# Schematic.net
KiCad netlist of a schematic drawn in EAGLE
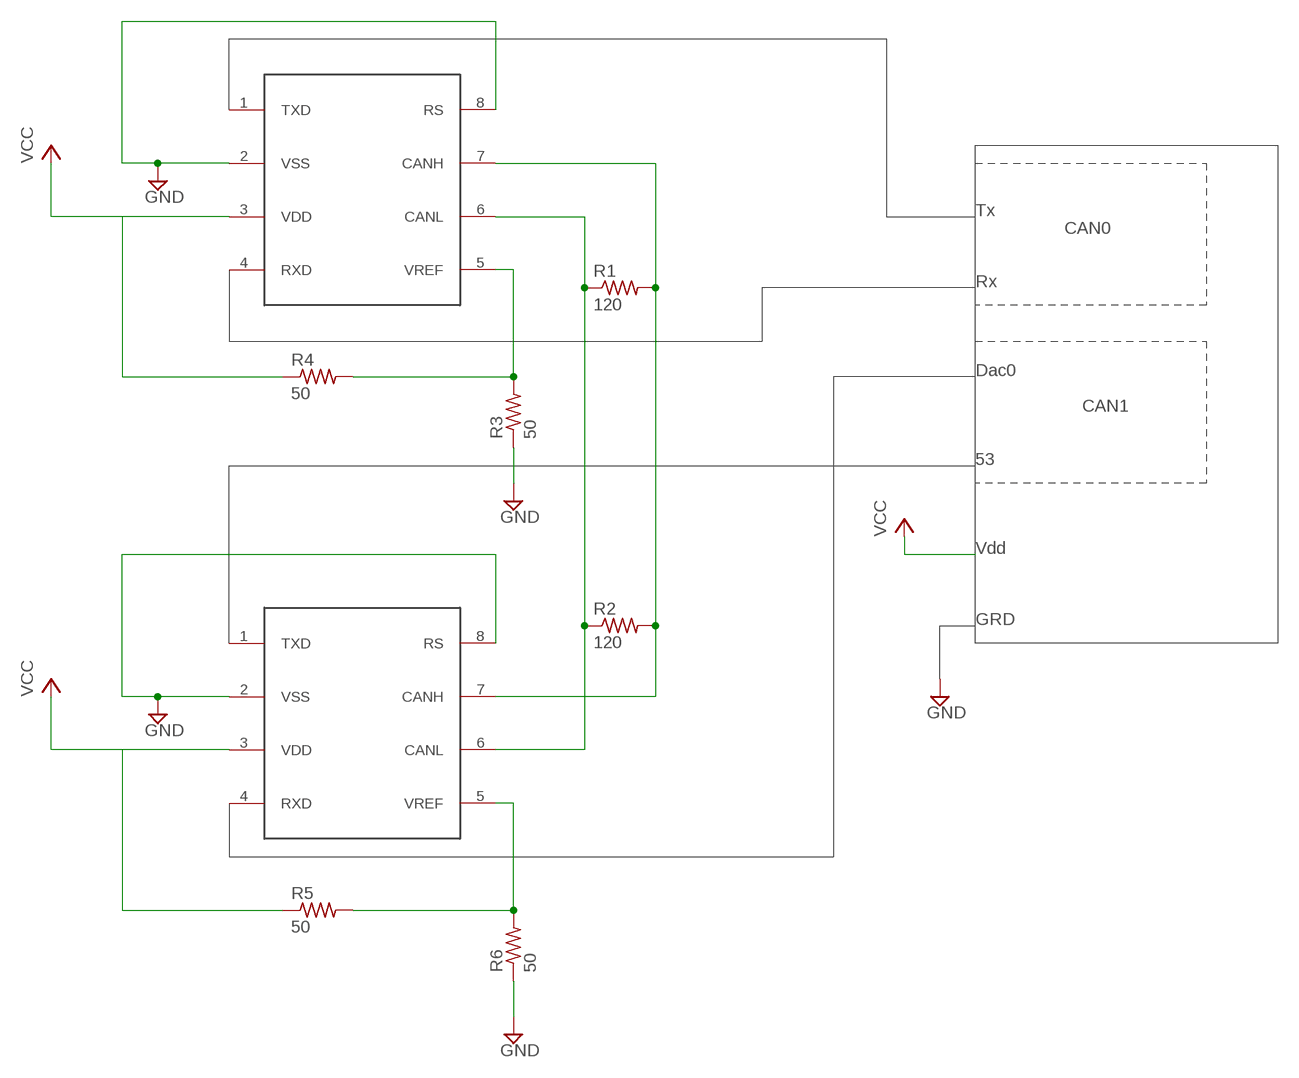
[diagram p0: schematic, sheet 1]

(export (version "E")
  (design (tool "Eeschema 10.0.6"))
  (components
    (comp (ref "R1")
      (value "120")
      (footprint "eagle-import:R0805")
      (libsource (lib "eagle-import") (part "RESISTOR"))
    )
    (comp (ref "R2")
      (value "120")
      (footprint "eagle-import:R0805")
      (libsource (lib "eagle-import") (part "RESISTOR"))
    )
    (comp (ref "R3")
      (value "50")
      (footprint "eagle-import:R0805")
      (libsource (lib "eagle-import") (part "RESISTOR"))
    )
    (comp (ref "R4")
      (value "50")
      (footprint "eagle-import:R0805")
      (libsource (lib "eagle-import") (part "RESISTOR"))
    )
    (comp (ref "R5")
      (value "50")
      (footprint "eagle-import:R0805")
      (libsource (lib "eagle-import") (part "RESISTOR"))
    )
    (comp (ref "R6")
      (value "50")
      (footprint "eagle-import:R0805")
      (libsource (lib "eagle-import") (part "RESISTOR"))
    )
    (comp (ref "U$1")
      (value "MCP2551")
      (footprint "eagle-import:SOIC8")
      (libsource (lib "eagle-import") (part "MCP2551"))
    )
    (comp (ref "U$4")
      (value "MCP2551")
      (footprint "eagle-import:SOIC8")
      (libsource (lib "eagle-import") (part "MCP2551"))
    )
  )
  (nets
    (net (code "1") (name "GND") (class "Default")
      (node (ref "R3") (pin "1") (pinfunction "1_1") (pintype "passive"))
      (node (ref "R6") (pin "1") (pinfunction "1_1") (pintype "passive"))
      (node (ref "U$1") (pin "2") (pinfunction "VSS_2") (pintype "bidirectional"))
      (node (ref "U$1") (pin "8") (pinfunction "RS_8") (pintype "bidirectional"))
      (node (ref "U$4") (pin "2") (pinfunction "VSS_2") (pintype "bidirectional"))
      (node (ref "U$4") (pin "8") (pinfunction "RS_8") (pintype "bidirectional"))
    )
    (net (code "2") (name "Net-(U$1-CANH)") (class "Default")
      (node (ref "R1") (pin "2") (pinfunction "2_2") (pintype "passive"))
      (node (ref "R2") (pin "2") (pinfunction "2_2") (pintype "passive"))
      (node (ref "U$1") (pin "7") (pinfunction "CANH_7") (pintype "bidirectional"))
      (node (ref "U$4") (pin "7") (pinfunction "CANH_7") (pintype "bidirectional"))
    )
    (net (code "3") (name "Net-(U$1-CANL)") (class "Default")
      (node (ref "R1") (pin "1") (pinfunction "1_1") (pintype "passive"))
      (node (ref "R2") (pin "1") (pinfunction "1_1") (pintype "passive"))
      (node (ref "U$1") (pin "6") (pinfunction "CANL_6") (pintype "bidirectional"))
      (node (ref "U$4") (pin "6") (pinfunction "CANL_6") (pintype "bidirectional"))
    )
    (net (code "4") (name "Net-(U$1-VREF)") (class "Default")
      (node (ref "R3") (pin "2") (pinfunction "2_2") (pintype "passive"))
      (node (ref "R4") (pin "2") (pinfunction "2_2") (pintype "passive"))
      (node (ref "U$1") (pin "5") (pinfunction "VREF_5") (pintype "bidirectional"))
    )
    (net (code "5") (name "Net-(U$4-VREF)") (class "Default")
      (node (ref "R5") (pin "2") (pinfunction "2_2") (pintype "passive"))
      (node (ref "R6") (pin "2") (pinfunction "2_2") (pintype "passive"))
      (node (ref "U$4") (pin "5") (pinfunction "VREF_5") (pintype "bidirectional"))
    )
    (net (code "6") (name "VCC") (class "Default")
      (node (ref "R4") (pin "1") (pinfunction "1_1") (pintype "passive"))
      (node (ref "R5") (pin "1") (pinfunction "1_1") (pintype "passive"))
      (node (ref "U$1") (pin "3") (pinfunction "VDD_3") (pintype "bidirectional"))
      (node (ref "U$4") (pin "3") (pinfunction "VDD_3") (pintype "bidirectional"))
    )
    (net (code "7") (name "unconnected-(U$1-RXD-Pad4)") (class "Default")
      (node (ref "U$1") (pin "4") (pinfunction "RXD_4") (pintype "bidirectional"))
    )
    (net (code "8") (name "unconnected-(U$1-TXD-Pad1)") (class "Default")
      (node (ref "U$1") (pin "1") (pinfunction "TXD_1") (pintype "bidirectional"))
    )
    (net (code "9") (name "unconnected-(U$4-RXD-Pad4)") (class "Default")
      (node (ref "U$4") (pin "4") (pinfunction "RXD_4") (pintype "bidirectional"))
    )
    (net (code "10") (name "unconnected-(U$4-TXD-Pad1)") (class "Default")
      (node (ref "U$4") (pin "1") (pinfunction "TXD_1") (pintype "bidirectional"))
    )
  )
)
